# power_curr_mon.net
KiCad netlist of a schematic drawn in Altium Designer
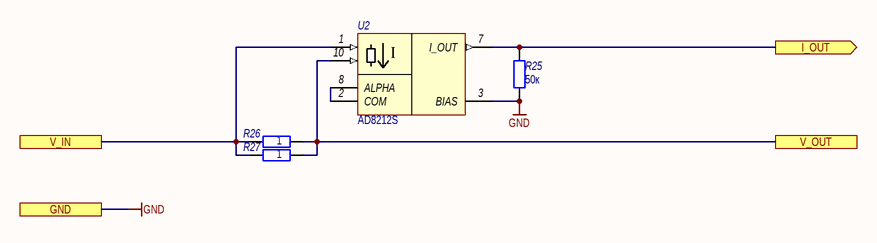
[diagram p0: power_curr_mon.SchDoc]

(export (version "E")
  (design (tool "Eeschema 10.0.6"))
  (components
    (comp (ref "R25")
      (value "50к")
      (footprint "SMD_0805")
      (description "Resistor")
      (libsource (lib "Passive") (part "Resistor"))
    )
    (comp (ref "R26")
      (value "1")
      (footprint "SMD_1206")
      (description "Resistor")
      (libsource (lib "") (part "Resistor_1"))
    )
    (comp (ref "R27")
      (value "1")
      (footprint "SMD_1206")
      (description "Resistor")
      (libsource (lib "") (part "Resistor_1"))
    )
    (comp (ref "U2")
      (value "AD8212S")
      (footprint "FlatPack-10_MSOP-8")
      (libsource (lib "Power_Monitor") (part "AD8212S"))
    )
  )
  (nets
    (net (code "1") (name "/I_OUT") (class "Default")
      (node (ref "R25") (pin "2") (pinfunction "2_2") (pintype "passive"))
      (node (ref "U2") (pin "7") (pinfunction "I_OUT_7") (pintype "output"))
    )
    (net (code "2") (name "/V_IN") (class "Default")
      (node (ref "R26") (pin "1") (pinfunction "1_1") (pintype "passive"))
      (node (ref "R27") (pin "1") (pinfunction "1_1") (pintype "passive"))
      (node (ref "U2") (pin "1") (pinfunction "V+_1") (pintype "input"))
    )
    (net (code "3") (name "/V_OUT") (class "Default")
      (node (ref "R26") (pin "2") (pinfunction "2_2") (pintype "passive"))
      (node (ref "R27") (pin "2") (pinfunction "2_2") (pintype "passive"))
      (node (ref "U2") (pin "10") (pinfunction "V_SENSE_10") (pintype "input"))
    )
    (net (code "4") (name "GND") (class "Default")
      (node (ref "R25") (pin "1") (pinfunction "1_1") (pintype "passive"))
      (node (ref "U2") (pin "3") (pinfunction "BIAS_3") (pintype "open_collector"))
    )
    (net (code "5") (name "Net-(U2-ALPHA)") (class "Default")
      (node (ref "U2") (pin "2") (pinfunction "COM_2") (pintype "open_collector"))
      (node (ref "U2") (pin "8") (pinfunction "ALPHA_8") (pintype "open_collector"))
    )
  )
)
